# HandCream2040.net
KiCad netlist of a schematic drawn in EAGLE
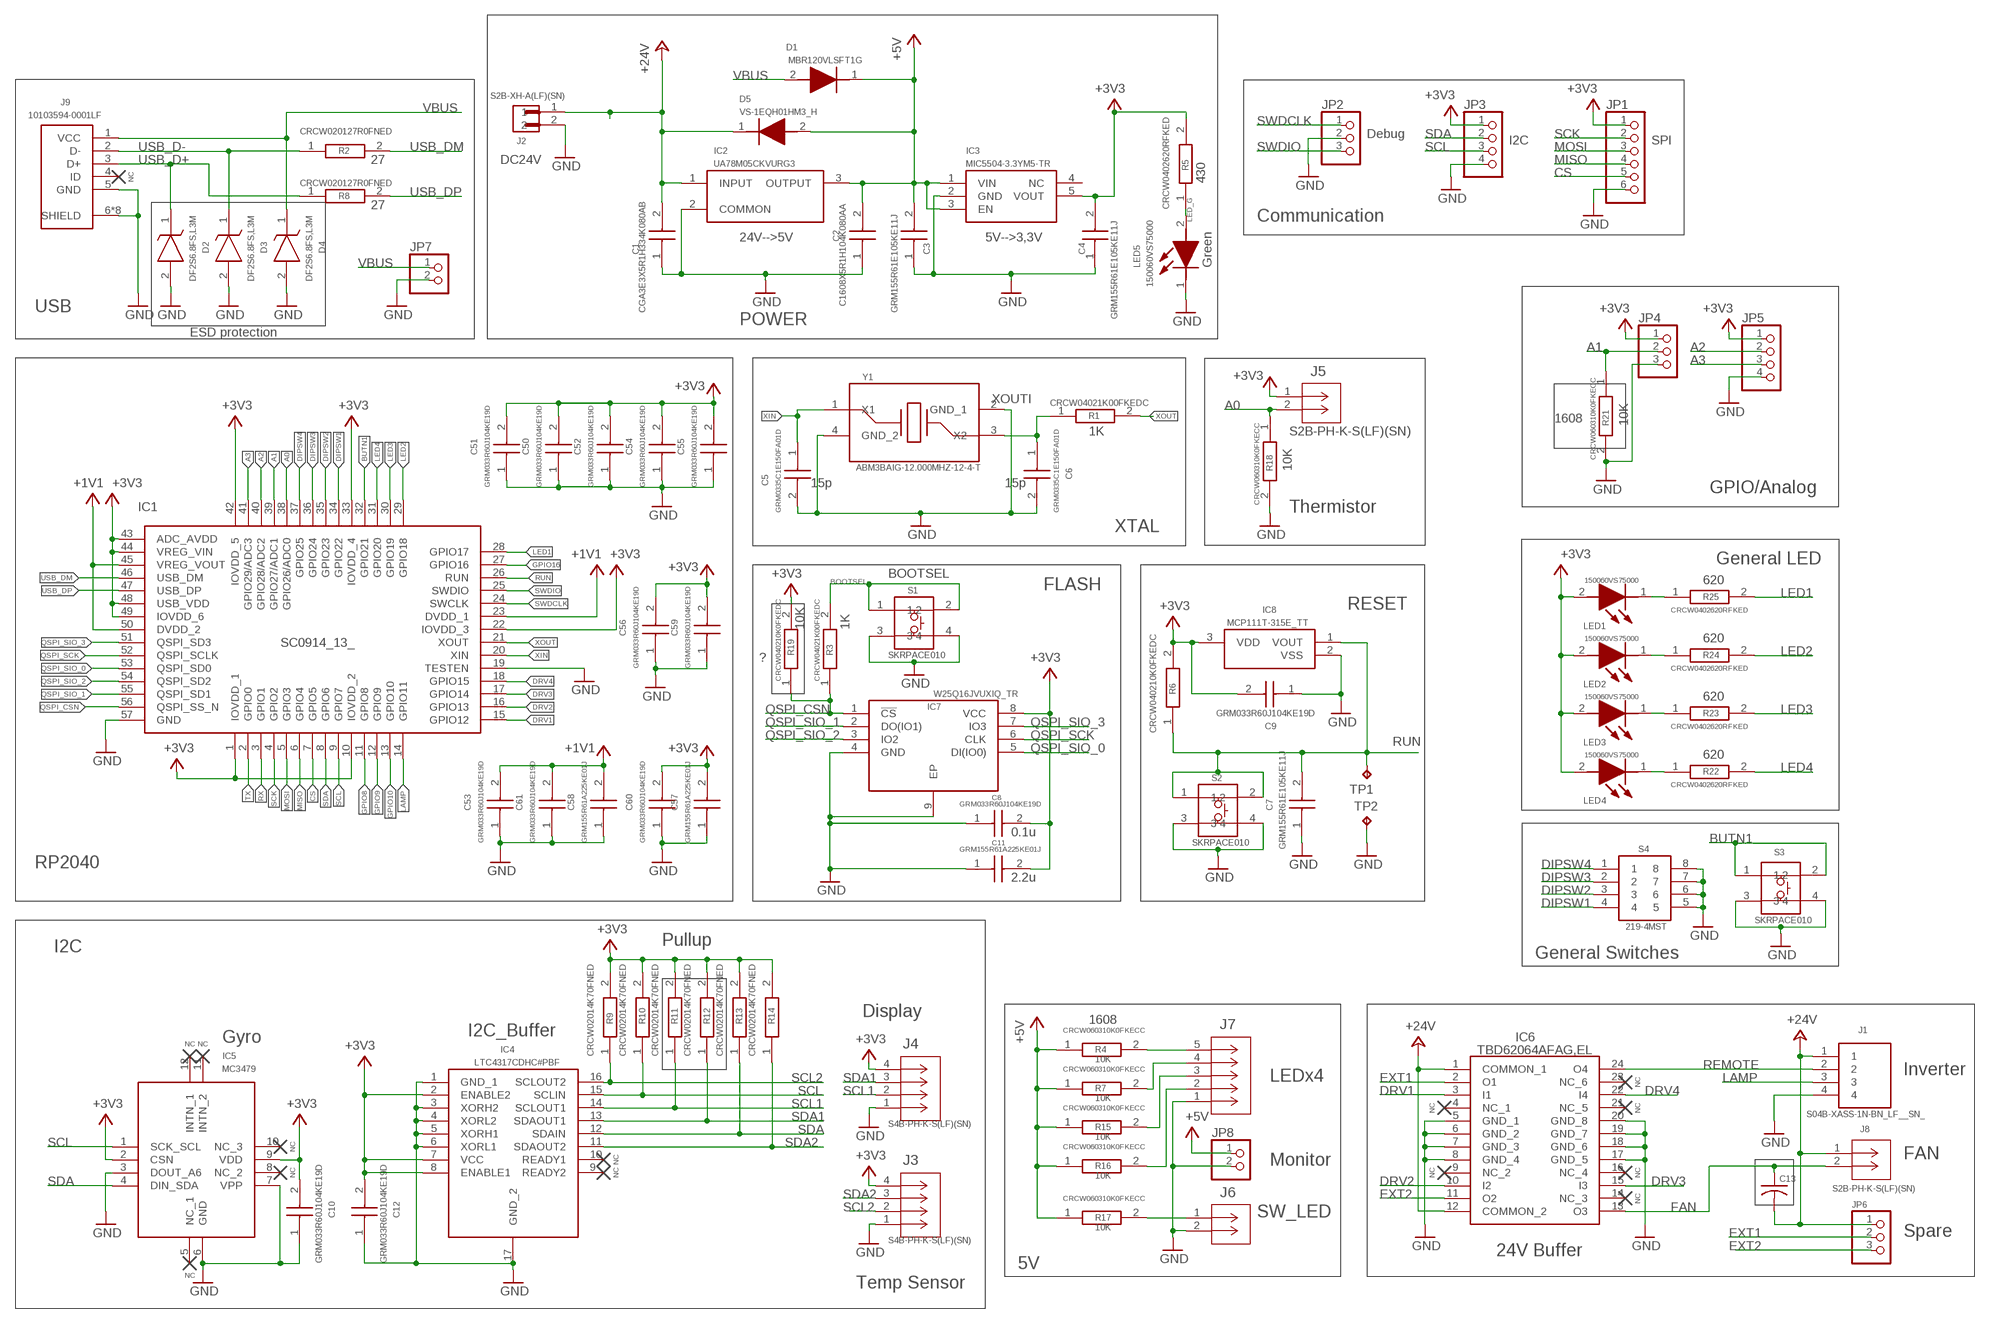
[diagram p0: schematic, sheet 1]

(export (version "E")
  (design (tool "Eeschema 10.0.6"))
  (components
    (comp (ref "C1")
      (value "CGA3E3X5R1H334K080AB")
      (footprint "eagle-import:CAPC1608X90N")
      (fields (field (name "MOUSER_PART_NUMBER") "810-CGA3E3X5R1H334KB"))
      (libsource (lib "eagle-import") (part "CGA3E3X5R1H334K080AB"))
    )
    (comp (ref "C2")
      (value "C1608X5R1H104K080AA")
      (footprint "eagle-import:CAPC1608X80N")
      (fields (field (name "MOUSER_PART_NUMBER") "810-C1608X5R1H104K"))
      (libsource (lib "eagle-import") (part "C1608X5R1H104K080AA"))
    )
    (comp (ref "C3")
      (value "GRM155R61E105KE11J")
      (footprint "eagle-import:CAPC1005X55N")
      (fields (field (name "MOUSER_PART_NUMBER") "81-GRM155R61E105KE1J"))
      (libsource (lib "eagle-import") (part "GRM155R61E105KE11J"))
    )
    (comp (ref "C4")
      (value "GRM155R61E105KE11J")
      (footprint "eagle-import:CAPC1005X55N")
      (fields (field (name "MOUSER_PART_NUMBER") "81-GRM155R61E105KE1J"))
      (libsource (lib "eagle-import") (part "GRM155R61E105KE11J"))
    )
    (comp (ref "C5")
      (value "GRM0335C1E150FA01D")
      (footprint "eagle-import:CAPC0603X33N")
      (fields (field (name "MOUSER_PART_NUMBER") "81-GRM0335C1E150FA1D") (field (name "C") "15p"))
      (libsource (lib "eagle-import") (part "GRM0335C1E150FA01D"))
    )
    (comp (ref "C6")
      (value "GRM0335C1E150FA01D")
      (footprint "eagle-import:CAPC0603X33N")
      (fields (field (name "MOUSER_PART_NUMBER") "81-GRM0335C1E150FA1D") (field (name "C") "15p"))
      (libsource (lib "eagle-import") (part "GRM0335C1E150FA01D"))
    )
    (comp (ref "C7")
      (value "GRM155R61E105KE11J")
      (footprint "eagle-import:CAPC1005X55N")
      (fields (field (name "MOUSER_PART_NUMBER") "81-GRM155R61E105KE1J"))
      (libsource (lib "eagle-import") (part "GRM155R61E105KE11J"))
    )
    (comp (ref "C8")
      (value "GRM033R60J104KE19D")
      (footprint "eagle-import:CAPC0603X33N")
      (fields (field (name "MOUSER_PART_NUMBER") "81-GRM033R60J104KE19") (field (name "C") "0.1u"))
      (libsource (lib "eagle-import") (part "GRM033R60J104KE19D"))
    )
    (comp (ref "C9")
      (value "GRM033R60J104KE19D")
      (footprint "eagle-import:CAPC0603X33N")
      (fields (field (name "MOUSER_PART_NUMBER") "81-GRM033R60J104KE19"))
      (libsource (lib "eagle-import") (part "GRM033R60J104KE19D"))
    )
    (comp (ref "C10")
      (value "GRM033R60J104KE19D")
      (footprint "eagle-import:CAPC0603X33N")
      (fields (field (name "MOUSER_PART_NUMBER") "81-GRM033R60J104KE19"))
      (libsource (lib "eagle-import") (part "GRM033R60J104KE19D"))
    )
    (comp (ref "C11")
      (value "GRM155R61A225KE01J")
      (footprint "eagle-import:CAPC1005X55N")
      (fields (field (name "MOUSER_PART_NUMBER") "81-GRM155R61A225K01J") (field (name "C") "2.2u"))
      (libsource (lib "eagle-import") (part "GRM155R61A225KE01J"))
    )
    (comp (ref "C12")
      (value "GRM033R60J104KE19D")
      (footprint "eagle-import:CAPC0603X33N")
      (fields (field (name "MOUSER_PART_NUMBER") "81-GRM033R60J104KE19"))
      (libsource (lib "eagle-import") (part "GRM033R60J104KE19D"))
    )
    (comp (ref "C13")
      (value "C-US025-024X044")
      (footprint "eagle-import:C025-024X044")
      (libsource (lib "eagle-import") (part "C-US025-024X044"))
    )
    (comp (ref "C50")
      (value "GRM033R60J104KE19D")
      (footprint "eagle-import:CAPC0603X33N")
      (fields (field (name "MOUSER_PART_NUMBER") "81-GRM033R60J104KE19"))
      (libsource (lib "eagle-import") (part "GRM033R60J104KE19D"))
    )
    (comp (ref "C51")
      (value "GRM033R60J104KE19D")
      (footprint "eagle-import:CAPC0603X33N")
      (fields (field (name "MOUSER_PART_NUMBER") "81-GRM033R60J104KE19"))
      (libsource (lib "eagle-import") (part "GRM033R60J104KE19D"))
    )
    (comp (ref "C52")
      (value "GRM033R60J104KE19D")
      (footprint "eagle-import:CAPC0603X33N")
      (fields (field (name "MOUSER_PART_NUMBER") "81-GRM033R60J104KE19"))
      (libsource (lib "eagle-import") (part "GRM033R60J104KE19D"))
    )
    (comp (ref "C53")
      (value "GRM033R60J104KE19D")
      (footprint "eagle-import:CAPC0603X33N")
      (fields (field (name "MOUSER_PART_NUMBER") "81-GRM033R60J104KE19"))
      (libsource (lib "eagle-import") (part "GRM033R60J104KE19D"))
    )
    (comp (ref "C54")
      (value "GRM033R60J104KE19D")
      (footprint "eagle-import:CAPC0603X33N")
      (fields (field (name "MOUSER_PART_NUMBER") "81-GRM033R60J104KE19"))
      (libsource (lib "eagle-import") (part "GRM033R60J104KE19D"))
    )
    (comp (ref "C55")
      (value "GRM033R60J104KE19D")
      (footprint "eagle-import:CAPC0603X33N")
      (fields (field (name "MOUSER_PART_NUMBER") "81-GRM033R60J104KE19"))
      (libsource (lib "eagle-import") (part "GRM033R60J104KE19D"))
    )
    (comp (ref "C56")
      (value "GRM033R60J104KE19D")
      (footprint "eagle-import:CAPC0603X33N")
      (fields (field (name "MOUSER_PART_NUMBER") "81-GRM033R60J104KE19"))
      (libsource (lib "eagle-import") (part "GRM033R60J104KE19D"))
    )
    (comp (ref "C57")
      (value "GRM155R61A225KE01J")
      (footprint "eagle-import:CAPC1005X55N")
      (fields (field (name "MOUSER_PART_NUMBER") "81-GRM155R61A225K01J"))
      (libsource (lib "eagle-import") (part "GRM155R61A225KE01J"))
    )
    (comp (ref "C58")
      (value "GRM155R61A225KE01J")
      (footprint "eagle-import:CAPC1005X55N")
      (fields (field (name "MOUSER_PART_NUMBER") "81-GRM155R61A225K01J"))
      (libsource (lib "eagle-import") (part "GRM155R61A225KE01J"))
    )
    (comp (ref "C59")
      (value "GRM033R60J104KE19D")
      (footprint "eagle-import:CAPC0603X33N")
      (fields (field (name "MOUSER_PART_NUMBER") "81-GRM033R60J104KE19"))
      (libsource (lib "eagle-import") (part "GRM033R60J104KE19D"))
    )
    (comp (ref "C60")
      (value "GRM033R60J104KE19D")
      (footprint "eagle-import:CAPC0603X33N")
      (fields (field (name "MOUSER_PART_NUMBER") "81-GRM033R60J104KE19"))
      (libsource (lib "eagle-import") (part "GRM033R60J104KE19D"))
    )
    (comp (ref "C61")
      (value "GRM033R60J104KE19D")
      (footprint "eagle-import:CAPC0603X33N")
      (fields (field (name "MOUSER_PART_NUMBER") "81-GRM033R60J104KE19"))
      (libsource (lib "eagle-import") (part "GRM033R60J104KE19D"))
    )
    (comp (ref "D1")
      (value "MBR120VLSFT1G")
      (footprint "eagle-import:SODFL3616X98N")
      (fields (field (name "MOUSER_PART_NUMBER") "863-MBR120VLSFT1G"))
      (libsource (lib "eagle-import") (part "MBR120VLSFT1G"))
    )
    (comp (ref "D2")
      (value "DF2S6.8FS,L3M")
      (footprint "eagle-import:SODFL1006X45N")
      (fields (field (name "MOUSER_PART_NUMBER") "757-DF2S68FSL3M"))
      (libsource (lib "eagle-import") (part "DF2S6.8FS,L3M"))
    )
    (comp (ref "D3")
      (value "DF2S6.8FS,L3M")
      (footprint "eagle-import:SODFL1006X45N")
      (fields (field (name "MOUSER_PART_NUMBER") "757-DF2S68FSL3M"))
      (libsource (lib "eagle-import") (part "DF2S6.8FS,L3M"))
    )
    (comp (ref "D4")
      (value "DF2S6.8FS,L3M")
      (footprint "eagle-import:SODFL1006X45N")
      (fields (field (name "MOUSER_PART_NUMBER") "757-DF2S68FSL3M"))
      (libsource (lib "eagle-import") (part "DF2S6.8FS,L3M"))
    )
    (comp (ref "D5")
      (value "VS-1EQH01HM3_H")
      (footprint "eagle-import:VS1EQH01HM3H")
      (fields
        (field (name "MANUFACTURER_PART_NUMBER") "VS-1EQH01HM3/H")
        (field (name "MOUSER_PART_NUMBER") "78-VS-1EQH01HM3/H")
      )
      (libsource (lib "eagle-import") (part "VS-1EQH01HM3_H"))
    )
    (comp (ref "IC1")
      (value "SC0914_13_")
      (footprint "eagle-import:SC091413")
      (fields
        (field (name "MANUFACTURER_PART_NUMBER") "SC0914(13)")
        (field (name "MOUSER_PART_NUMBER") "358-SC091413")
      )
      (libsource (lib "eagle-import") (part "SC0914_13_"))
    )
    (comp (ref "IC2")
      (value "UA78M05CKVURG3")
      (footprint "eagle-import:TPS7A6533QKVURQ1")
      (fields (field (name "MOUSER_PART_NUMBER") "595-UA78M05CKVURG3"))
      (libsource (lib "eagle-import") (part "UA78M05CKVURG3"))
    )
    (comp (ref "IC3")
      (value "MIC5504-3.3YM5-TR")
      (footprint "eagle-import:SOT95P280X145-5N")
      (fields (field (name "MOUSER_PART_NUMBER") "998-MIC5504-3.3YM5TR"))
      (libsource (lib "eagle-import") (part "MIC5504-3.3YM5-TR"))
    )
    (comp (ref "IC4")
      (value "LTC4317CDHC#PBF")
      (footprint "eagle-import:SON50P300X500X80-17N")
      (fields (field (name "MOUSER_PART_NUMBER") "584-LTC4317CDHC#PBF"))
      (libsource (lib "eagle-import") (part "LTC4317CDHC#PBF"))
    )
    (comp (ref "IC5")
      (value "MC3479")
      (footprint "eagle-import:MC3479")
      (fields (field (name "MOUSER_PART_NUMBER") "498-MC3479"))
      (libsource (lib "eagle-import") (part "MC3479"))
    )
    (comp (ref "IC6")
      (value "TBD62064AFAG,EL")
      (footprint "eagle-import:SOP100P800X190-24N")
      (fields (field (name "MOUSER_PART_NUMBER") "757-TBD62064AFAGEHZ"))
      (libsource (lib "eagle-import") (part "TBD62064AFAG,EL"))
    )
    (comp (ref "IC7")
      (value "W25Q16JVUXIQ_TR")
      (footprint "eagle-import:SON50P300X200X60-9N")
      (fields
        (field (name "MANUFACTURER_PART_NUMBER") "W25Q16JVUXIQ TR")
        (field (name "MOUSER_PART_NUMBER") "454-W25Q16JVUXIQTR")
      )
      (libsource (lib "eagle-import") (part "W25Q16JVUXIQ_TR"))
    )
    (comp (ref "IC8")
      (value "MCP111T-315E_TT")
      (footprint "eagle-import:SOT96P237X112-3N")
      (fields
        (field (name "MANUFACTURER_PART_NUMBER") "MCP111T-315E/TT")
        (field (name "MOUSER_PART_NUMBER") "579-MCP111T-315E/TT")
      )
      (libsource (lib "eagle-import") (part "MCP111T-315E_TT"))
    )
    (comp (ref "J1")
      (value "S04B-XASS-1N-BN_LF__SN_")
      (footprint "eagle-import:S04BXASS1NBNLFSN")
      (fields (field (name "MANUFACTURER_PART_NUMBER") "S04B-XASS-1N-BN(LF)(SN)"))
      (libsource (lib "eagle-import") (part "S04B-XASS-1N-BN_LF__SN_"))
    )
    (comp (ref "J2")
      (value "S2B-XH-A(LF)(SN)")
      (footprint "eagle-import:JST_S2B-XH-A(LF)(SN)")
      (fields (field (name "MF") "JST Sales"))
      (libsource (lib "eagle-import") (part "S2B-XH-A(LF)(SN)"))
    )
    (comp (ref "J3")
      (value "S4B-PH-K-S(LF)(SN)")
      (footprint "eagle-import:CONN_S4B-PH-K-S_JST")
      (fields
        (field (name "MANUFACTURER_PART_NUMBER") "S4B-PH-K-S(LF)(SN)")
        (field (name "COPYRIGHT") "Copyright (C) 2023 Ultra Librarian. All rights reserved.")
      )
      (libsource (lib "eagle-import") (part "S4B-PH-K-S(LF)(SN)"))
    )
    (comp (ref "J4")
      (value "S4B-PH-K-S(LF)(SN)")
      (footprint "eagle-import:CONN_S4B-PH-K-S_JST")
      (fields
        (field (name "MANUFACTURER_PART_NUMBER") "S4B-PH-K-S(LF)(SN)")
        (field (name "COPYRIGHT") "Copyright (C) 2023 Ultra Librarian. All rights reserved.")
      )
      (libsource (lib "eagle-import") (part "S4B-PH-K-S(LF)(SN)"))
    )
    (comp (ref "J5")
      (value "S2B-PH-K-S(LF)(SN)")
      (footprint "eagle-import:CONN_S2B-PH-K-S_JST")
      (fields
        (field (name "MANUFACTURER_PART_NUMBER") "S2B-PH-K-S(LF)(SN)")
        (field (name "COPYRIGHT") "Copyright (C) 2023 Ultra Librarian. All rights reserved.")
      )
      (libsource (lib "eagle-import") (part "S2B-PH-K-S(LF)(SN)"))
    )
    (comp (ref "J6")
      (value "S2B-PH-K-S(LF)(SN)")
      (footprint "eagle-import:CONN_S2B-PH-K-S_JST")
      (fields (field (name "COPYRIGHT") "Copyright (C) 2023 Ultra Librarian. All rights reserved."))
      (libsource (lib "eagle-import") (part "S2B-PH-K-S(LF)(SN)"))
    )
    (comp (ref "J7")
      (value "S5B-PH-K-S_(LF)(SN)")
      (footprint "eagle-import:CONN_S5B-PH-K-S_JST")
      (fields
        (field (name "MANUFACTURER_PART_NUMBER") "S5B-PH-K-S (LF)(SN)")
        (field (name "COPYRIGHT") "Copyright (C) 2023 Ultra Librarian. All rights reserved.")
      )
      (libsource (lib "eagle-import") (part "S5B-PH-K-S_(LF)(SN)"))
    )
    (comp (ref "J8")
      (value "S2B-PH-K-S(LF)(SN)")
      (footprint "eagle-import:CONN_S2B-PH-K-S_JST")
      (fields
        (field (name "MANUFACTURER_PART_NUMBER") "S2B-PH-K-S(LF)(SN)")
        (field (name "COPYRIGHT") "Copyright (C) 2023 Ultra Librarian. All rights reserved.")
      )
      (libsource (lib "eagle-import") (part "S2B-PH-K-S(LF)(SN)"))
    )
    (comp (ref "J9")
      (value "10103594-0001LF")
      (footprint "eagle-import:AMPHENOL_10103594-0001LF")
      (fields (field (name "DIGI-KEY_PART_NUMBER") "609-4050-2-ND") (field (name "MF") "Amphenol ICC"))
      (libsource (lib "eagle-import") (part "10103594-0001LF"))
    )
    (comp (ref "JP1")
      (value "PINHD-1X6")
      (footprint "eagle-import:1X06")
      (libsource (lib "eagle-import") (part "PINHD-1X6"))
    )
    (comp (ref "JP2")
      (value "PINHD-1X3")
      (footprint "eagle-import:1X03")
      (libsource (lib "eagle-import") (part "PINHD-1X3"))
    )
    (comp (ref "JP3")
      (value "PINHD-1X4")
      (footprint "eagle-import:1X04")
      (libsource (lib "eagle-import") (part "PINHD-1X4"))
    )
    (comp (ref "JP4")
      (value "PINHD-1X3")
      (footprint "eagle-import:1X03")
      (libsource (lib "eagle-import") (part "PINHD-1X3"))
    )
    (comp (ref "JP5")
      (value "PINHD-1X4")
      (footprint "eagle-import:1X04")
      (libsource (lib "eagle-import") (part "PINHD-1X4"))
    )
    (comp (ref "JP6")
      (value "PINHD-1X3")
      (footprint "eagle-import:1X03")
      (libsource (lib "eagle-import") (part "PINHD-1X3"))
    )
    (comp (ref "JP7")
      (value "PINHD-1X2")
      (footprint "eagle-import:1X02")
      (libsource (lib "eagle-import") (part "PINHD-1X2"))
    )
    (comp (ref "JP8")
      (value "PINHD-1X2")
      (footprint "eagle-import:1X02")
      (libsource (lib "eagle-import") (part "PINHD-1X2"))
    )
    (comp (ref "LED1")
      (value "150060VS75000")
      (footprint "eagle-import:LEDC1608X80N")
      (fields (field (name "MOUSER_PART_NUMBER") "710-150060VS75000"))
      (libsource (lib "eagle-import") (part "150060VS75000"))
    )
    (comp (ref "LED2")
      (value "150060VS75000")
      (footprint "eagle-import:LEDC1608X80N")
      (fields (field (name "MOUSER_PART_NUMBER") "710-150060VS75000"))
      (libsource (lib "eagle-import") (part "150060VS75000"))
    )
    (comp (ref "LED3")
      (value "150060VS75000")
      (footprint "eagle-import:LEDC1608X80N")
      (fields (field (name "MOUSER_PART_NUMBER") "710-150060VS75000"))
      (libsource (lib "eagle-import") (part "150060VS75000"))
    )
    (comp (ref "LED4")
      (value "150060VS75000")
      (footprint "eagle-import:LEDC1608X80N")
      (fields (field (name "MOUSER_PART_NUMBER") "710-150060VS75000"))
      (libsource (lib "eagle-import") (part "150060VS75000"))
    )
    (comp (ref "LED5")
      (value "150060VS75000")
      (footprint "eagle-import:LEDC1608X80N")
      (fields (field (name "MOUSER_PART_NUMBER") "710-150060VS75000"))
      (libsource (lib "eagle-import") (part "150060VS75000"))
    )
    (comp (ref "R1")
      (value "CRCW04021K00FKEDC")
      (footprint "eagle-import:RESC1005X35N")
      (fields (field (name "MOUSER_PART_NUMBER") "71-CRCW04021K00FKEDC") (field (name "R") "1K"))
      (libsource (lib "eagle-import") (part "CRCW04021K00FKEDC"))
    )
    (comp (ref "R2")
      (value "CRCW020127R0FNED")
      (footprint "eagle-import:RESC0603X28N")
      (fields (field (name "MOUSER_PART_NUMBER") "71-CRCW020127R0FNED") (field (name "R") "27"))
      (libsource (lib "eagle-import") (part "CRCW020127R0FNED"))
    )
    (comp (ref "R3")
      (value "CRCW04021K00FKEDC")
      (footprint "eagle-import:RESC1005X35N")
      (fields (field (name "MOUSER_PART_NUMBER") "71-CRCW04021K00FKEDC") (field (name "R") "1K"))
      (libsource (lib "eagle-import") (part "CRCW04021K00FKEDC"))
    )
    (comp (ref "R4")
      (value "CRCW060310K0FKECC")
      (footprint "eagle-import:RESC1608X55N")
      (fields (field (name "MOUSER_PART_NUMBER") "71-CRCW060310K0FKECC") (field (name "R") "10K"))
      (libsource (lib "eagle-import") (part "CRCW060310K0FKECC"))
    )
    (comp (ref "R5")
      (value "CRCW0402620RFKED")
      (footprint "eagle-import:RESC1005X40N")
      (fields (field (name "MOUSER_PART_NUMBER") "71-CRCW0402-620-E3") (field (name "R") "430"))
      (libsource (lib "eagle-import") (part "CRCW0402620RFKED"))
    )
    (comp (ref "R6")
      (value "CRCW040210K0FKEDC")
      (footprint "eagle-import:RESC1005X35N")
      (fields (field (name "MOUSER_PART_NUMBER") "71-CRCW040210K0FKEDC"))
      (libsource (lib "eagle-import") (part "CRCW040210K0FKEDC"))
    )
    (comp (ref "R7")
      (value "CRCW060310K0FKECC")
      (footprint "eagle-import:RESC1608X55N")
      (fields (field (name "MOUSER_PART_NUMBER") "71-CRCW060310K0FKECC") (field (name "R") "10K"))
      (libsource (lib "eagle-import") (part "CRCW060310K0FKECC"))
    )
    (comp (ref "R8")
      (value "CRCW020127R0FNED")
      (footprint "eagle-import:RESC0603X28N")
      (fields (field (name "MOUSER_PART_NUMBER") "71-CRCW020127R0FNED") (field (name "R") "27"))
      (libsource (lib "eagle-import") (part "CRCW020127R0FNED"))
    )
    (comp (ref "R9")
      (value "CRCW02014K70FNED")
      (footprint "eagle-import:RESC0603X28N")
      (fields (field (name "MOUSER_PART_NUMBER") "71-CRCW02014K70FNED"))
      (libsource (lib "eagle-import") (part "CRCW02014K70FNED"))
    )
    (comp (ref "R10")
      (value "CRCW02014K70FNED")
      (footprint "eagle-import:RESC0603X28N")
      (fields (field (name "MOUSER_PART_NUMBER") "71-CRCW02014K70FNED"))
      (libsource (lib "eagle-import") (part "CRCW02014K70FNED"))
    )
    (comp (ref "R11")
      (value "CRCW02014K70FNED")
      (footprint "eagle-import:RESC0603X28N")
      (fields (field (name "MOUSER_PART_NUMBER") "71-CRCW02014K70FNED"))
      (libsource (lib "eagle-import") (part "CRCW02014K70FNED"))
    )
    (comp (ref "R12")
      (value "CRCW02014K70FNED")
      (footprint "eagle-import:RESC0603X28N")
      (fields (field (name "MOUSER_PART_NUMBER") "71-CRCW02014K70FNED"))
      (libsource (lib "eagle-import") (part "CRCW02014K70FNED"))
    )
    (comp (ref "R13")
      (value "CRCW02014K70FNED")
      (footprint "eagle-import:RESC0603X28N")
      (fields (field (name "MOUSER_PART_NUMBER") "71-CRCW02014K70FNED"))
      (libsource (lib "eagle-import") (part "CRCW02014K70FNED"))
    )
    (comp (ref "R14")
      (value "CRCW02014K70FNED")
      (footprint "eagle-import:RESC0603X28N")
      (fields (field (name "MOUSER_PART_NUMBER") "71-CRCW02014K70FNED"))
      (libsource (lib "eagle-import") (part "CRCW02014K70FNED"))
    )
    (comp (ref "R15")
      (value "CRCW060310K0FKECC")
      (footprint "eagle-import:RESC1608X55N")
      (fields (field (name "MOUSER_PART_NUMBER") "71-CRCW060310K0FKECC") (field (name "R") "10K"))
      (libsource (lib "eagle-import") (part "CRCW060310K0FKECC"))
    )
    (comp (ref "R16")
      (value "CRCW060310K0FKECC")
      (footprint "eagle-import:RESC1608X55N")
      (fields (field (name "MOUSER_PART_NUMBER") "71-CRCW060310K0FKECC") (field (name "R") "10K"))
      (libsource (lib "eagle-import") (part "CRCW060310K0FKECC"))
    )
    (comp (ref "R17")
      (value "CRCW060310K0FKECC")
      (footprint "eagle-import:RESC1608X55N")
      (fields (field (name "MOUSER_PART_NUMBER") "71-CRCW060310K0FKECC") (field (name "R") "10K"))
      (libsource (lib "eagle-import") (part "CRCW060310K0FKECC"))
    )
    (comp (ref "R18")
      (value "CRCW060310K0FKECC")
      (footprint "eagle-import:RESC1608X55N")
      (fields (field (name "MOUSER_PART_NUMBER") "71-CRCW060310K0FKECC") (field (name "R") "10K"))
      (libsource (lib "eagle-import") (part "CRCW060310K0FKECC"))
    )
    (comp (ref "R19")
      (value "CRCW040210K0FKEDC")
      (footprint "eagle-import:RESC1005X35N")
      (fields (field (name "MOUSER_PART_NUMBER") "71-CRCW040210K0FKEDC") (field (name "R") "10K"))
      (libsource (lib "eagle-import") (part "CRCW040210K0FKEDC"))
    )
    (comp (ref "R21")
      (value "CRCW060310K0FKECC")
      (footprint "eagle-import:RESC1608X55N")
      (fields (field (name "MOUSER_PART_NUMBER") "71-CRCW060310K0FKECC") (field (name "R") "10K"))
      (libsource (lib "eagle-import") (part "CRCW060310K0FKECC"))
    )
    (comp (ref "R22")
      (value "CRCW0402620RFKED")
      (footprint "eagle-import:RESC1005X40N")
      (fields (field (name "MOUSER_PART_NUMBER") "71-CRCW0402-620-E3") (field (name "R") "620"))
      (libsource (lib "eagle-import") (part "CRCW0402620RFKED"))
    )
    (comp (ref "R23")
      (value "CRCW0402620RFKED")
      (footprint "eagle-import:RESC1005X40N")
      (fields (field (name "MOUSER_PART_NUMBER") "71-CRCW0402-620-E3") (field (name "R") "620"))
      (libsource (lib "eagle-import") (part "CRCW0402620RFKED"))
    )
    (comp (ref "R24")
      (value "CRCW0402620RFKED")
      (footprint "eagle-import:RESC1005X40N")
      (fields (field (name "MOUSER_PART_NUMBER") "71-CRCW0402-620-E3") (field (name "R") "620"))
      (libsource (lib "eagle-import") (part "CRCW0402620RFKED"))
    )
    (comp (ref "R25")
      (value "CRCW0402620RFKED")
      (footprint "eagle-import:RESC1005X40N")
      (fields (field (name "MOUSER_PART_NUMBER") "71-CRCW0402-620-E3") (field (name "R") "620"))
      (libsource (lib "eagle-import") (part "CRCW0402620RFKED"))
    )
    (comp (ref "S1")
      (value "SKRPACE010")
      (footprint "eagle-import:SMT(4.2X3.2)")
      (fields (field (name "MOUSER_PART_NUMBER") "688-SKRPACE010"))
      (libsource (lib "eagle-import") (part "SKRPACE010"))
    )
    (comp (ref "S2")
      (value "SKRPACE010")
      (footprint "eagle-import:SMT(4.2X3.2)")
      (fields (field (name "MOUSER_PART_NUMBER") "688-SKRPACE010"))
      (libsource (lib "eagle-import") (part "SKRPACE010"))
    )
    (comp (ref "S3")
      (value "SKRPACE010")
      (footprint "eagle-import:SMT(4.2X3.2)")
      (fields (field (name "MOUSER_PART_NUMBER") "688-SKRPACE010"))
      (libsource (lib "eagle-import") (part "SKRPACE010"))
    )
    (comp (ref "S4")
      (value "219-4MST")
      (footprint "eagle-import:2194MST")
      (fields (field (name "MOUSER_PART_NUMBER") "774-2194MST"))
      (libsource (lib "eagle-import") (part "219-4MST"))
    )
    (comp (ref "TP1")
      (value "TPB1,27")
      (footprint "eagle-import:B1,27")
      (libsource (lib "eagle-import") (part "TPB1,27"))
    )
    (comp (ref "TP2")
      (value "TPB1,27")
      (footprint "eagle-import:B1,27")
      (libsource (lib "eagle-import") (part "TPB1,27"))
    )
    (comp (ref "Y1")
      (value "ABM3BAIG-12.000MHZ-12-4-T")
      (footprint "eagle-import:ABM3BAIG")
      (fields (field (name "MOUSER_PART_NUMBER") "815-ABM3BAIG1212-4T"))
      (libsource (lib "eagle-import") (part "ABM3BAIG-12.000MHZ-12-4-T"))
    )
  )
  (nets
    (net (code "1") (name "+1V1") (class "Default")
      (node (ref "C53") (pin "2") (pinfunction "2_2") (pintype "bidirectional"))
      (node (ref "C58") (pin "2") (pinfunction "2_2") (pintype "bidirectional"))
      (node (ref "C61") (pin "2") (pinfunction "2_2") (pintype "bidirectional"))
      (node (ref "IC1") (pin "23") (pinfunction "DVDD_1_23") (pintype "bidirectional"))
      (node (ref "IC1") (pin "45") (pinfunction "VREG_VOUT_45") (pintype "bidirectional"))
      (node (ref "IC1") (pin "50") (pinfunction "DVDD_2_50") (pintype "bidirectional"))
    )
    (net (code "2") (name "+3V3") (class "Default")
      (node (ref "C10") (pin "2") (pinfunction "2_2") (pintype "bidirectional"))
      (node (ref "C11") (pin "2") (pinfunction "2_2") (pintype "bidirectional"))
      (node (ref "C12") (pin "2") (pinfunction "2_2") (pintype "bidirectional"))
      (node (ref "C4") (pin "2") (pinfunction "2_2") (pintype "bidirectional"))
      (node (ref "C50") (pin "2") (pinfunction "2_2") (pintype "bidirectional"))
      (node (ref "C51") (pin "2") (pinfunction "2_2") (pintype "bidirectional"))
      (node (ref "C52") (pin "2") (pinfunction "2_2") (pintype "bidirectional"))
      (node (ref "C54") (pin "2") (pinfunction "2_2") (pintype "bidirectional"))
      (node (ref "C55") (pin "2") (pinfunction "2_2") (pintype "bidirectional"))
      (node (ref "C56") (pin "2") (pinfunction "2_2") (pintype "bidirectional"))
      (node (ref "C57") (pin "2") (pinfunction "2_2") (pintype "bidirectional"))
      (node (ref "C59") (pin "2") (pinfunction "2_2") (pintype "bidirectional"))
      (node (ref "C60") (pin "2") (pinfunction "2_2") (pintype "bidirectional"))
      (node (ref "C8") (pin "2") (pinfunction "2_2") (pintype "bidirectional"))
      (node (ref "C9") (pin "2") (pinfunction "2_2") (pintype "bidirectional"))
      (node (ref "IC1") (pin "1") (pinfunction "IOVDD_1_1") (pintype "bidirectional"))
      (node (ref "IC1") (pin "10") (pinfunction "IOVDD_2_10") (pintype "bidirectional"))
      (node (ref "IC1") (pin "22") (pinfunction "IOVDD_3_22") (pintype "bidirectional"))
      (node (ref "IC1") (pin "33") (pinfunction "IOVDD_4_33") (pintype "bidirectional"))
      (node (ref "IC1") (pin "42") (pinfunction "IOVDD_5_42") (pintype "bidirectional"))
      (node (ref "IC1") (pin "43") (pinfunction "ADC_AVDD_43") (pintype "bidirectional"))
      (node (ref "IC1") (pin "44") (pinfunction "VREG_VIN_44") (pintype "bidirectional"))
      (node (ref "IC1") (pin "48") (pinfunction "USB_VDD_48") (pintype "bidirectional"))
      (node (ref "IC1") (pin "49") (pinfunction "IOVDD_6_49") (pintype "bidirectional"))
      (node (ref "IC3") (pin "5") (pinfunction "VOUT_5") (pintype "bidirectional"))
      (node (ref "IC4") (pin "2") (pinfunction "ENABLE2_2") (pintype "bidirectional"))
      (node (ref "IC4") (pin "7") (pinfunction "VCC_7") (pintype "bidirectional"))
      (node (ref "IC4") (pin "8") (pinfunction "ENABLE1_8") (pintype "bidirectional"))
      (node (ref "IC5") (pin "2") (pinfunction "CSN_2") (pintype "bidirectional"))
      (node (ref "IC5") (pin "9") (pinfunction "VDD_9") (pintype "bidirectional"))
      (node (ref "IC7") (pin "8") (pinfunction "VCC_8") (pintype "bidirectional"))
      (node (ref "IC8") (pin "3") (pinfunction "VDD_3") (pintype "bidirectional"))
      (node (ref "J3") (pin "4") (pinfunction "4_4") (pintype "passive"))
      (node (ref "J4") (pin "4") (pinfunction "4_4") (pintype "passive"))
      (node (ref "J5") (pin "1") (pinfunction "1_1") (pintype "passive"))
      (node (ref "JP1") (pin "1") (pinfunction "1_1") (pintype "passive"))
      (node (ref "JP3") (pin "1") (pinfunction "1_1") (pintype "passive"))
      (node (ref "JP4") (pin "1") (pinfunction "1_1") (pintype "passive"))
      (node (ref "JP5") (pin "1") (pinfunction "1_1") (pintype "passive"))
      (node (ref "LED1") (pin "2") (pinfunction "A_2") (pintype "bidirectional"))
      (node (ref "LED2") (pin "2") (pinfunction "A_2") (pintype "bidirectional"))
      (node (ref "LED3") (pin "2") (pinfunction "A_2") (pintype "bidirectional"))
      (node (ref "LED4") (pin "2") (pinfunction "A_2") (pintype "bidirectional"))
      (node (ref "R10") (pin "2") (pinfunction "2_2") (pintype "bidirectional"))
      (node (ref "R11") (pin "2") (pinfunction "2_2") (pintype "bidirectional"))
      (node (ref "R12") (pin "2") (pinfunction "2_2") (pintype "bidirectional"))
      (node (ref "R13") (pin "2") (pinfunction "2_2") (pintype "bidirectional"))
      (node (ref "R14") (pin "2") (pinfunction "2_2") (pintype "bidirectional"))
      (node (ref "R19") (pin "2") (pinfunction "2_2") (pintype "bidirectional"))
      (node (ref "R5") (pin "2") (pinfunction "2_2") (pintype "bidirectional"))
      (node (ref "R6") (pin "2") (pinfunction "2_2") (pintype "bidirectional"))
      (node (ref "R9") (pin "2") (pinfunction "2_2") (pintype "bidirectional"))
    )
    (net (code "3") (name "+5V") (class "Default")
      (node (ref "C2") (pin "2") (pinfunction "2_2") (pintype "bidirectional"))
      (node (ref "C3") (pin "2") (pinfunction "2_2") (pintype "bidirectional"))
      (node (ref "D1") (pin "1") (pinfunction "K_1") (pintype "bidirectional"))
      (node (ref "D5") (pin "2") (pinfunction "A_2") (pintype "bidirectional"))
      (node (ref "IC2") (pin "3") (pinfunction "OUTPUT_3") (pintype "bidirectional"))
      (node (ref "IC3") (pin "1") (pinfunction "VIN_1") (pintype "bidirectional"))
      (node (ref "IC3") (pin "3") (pinfunction "EN_3") (pintype "bidirectional"))
      (node (ref "JP8") (pin "1") (pinfunction "1_1") (pintype "passive"))
      (node (ref "R15") (pin "1") (pinfunction "1_1") (pintype "bidirectional"))
      (node (ref "R16") (pin "1") (pinfunction "1_1") (pintype "bidirectional"))
      (node (ref "R17") (pin "1") (pinfunction "1_1") (pintype "bidirectional"))
      (node (ref "R4") (pin "1") (pinfunction "1_1") (pintype "bidirectional"))
      (node (ref "R7") (pin "1") (pinfunction "1_1") (pintype "bidirectional"))
    )
    (net (code "4") (name "+24V") (class "Default")
      (node (ref "C1") (pin "2") (pinfunction "2_2") (pintype "bidirectional"))
      (node (ref "C13") (pin "2") (pinfunction "2_2") (pintype "passive"))
      (node (ref "D5") (pin "1") (pinfunction "K_1") (pintype "bidirectional"))
      (node (ref "IC2") (pin "1") (pinfunction "INPUT_1") (pintype "bidirectional"))
      (node (ref "IC6") (pin "1") (pinfunction "COMMON_1_1") (pintype "bidirectional"))
      (node (ref "IC6") (pin "12") (pinfunction "COMMON_2_12") (pintype "bidirectional"))
      (node (ref "J1") (pin "1") (pinfunction "1_1") (pintype "bidirectional"))
      (node (ref "J2") (pin "1") (pinfunction "1_1") (pintype "passive"))
      (node (ref "J8") (pin "1") (pinfunction "1_1") (pintype "passive"))
      (node (ref "JP6") (pin "1") (pinfunction "1_1") (pintype "passive"))
    )
    (net (code "5") (name "/BOOTSEL") (class "Default")
      (node (ref "R3") (pin "2") (pinfunction "2_2") (pintype "bidirectional"))
      (node (ref "S1") (pin "1") (pinfunction "1_1") (pintype "bidirectional"))
      (node (ref "S1") (pin "2") (pinfunction "2_2") (pintype "bidirectional"))
    )
    (net (code "6") (name "/EXT1") (class "Default")
      (node (ref "IC6") (pin "2") (pinfunction "O1_2") (pintype "bidirectional"))
      (node (ref "JP6") (pin "2") (pinfunction "2_2") (pintype "passive"))
    )
    (net (code "7") (name "/EXT2") (class "Default")
      (node (ref "IC6") (pin "11") (pinfunction "O2_11") (pintype "bidirectional"))
      (node (ref "JP6") (pin "3") (pinfunction "3_3") (pintype "passive"))
    )
    (net (code "8") (name "/FAN") (class "Default")
      (node (ref "C13") (pin "1") (pinfunction "1_1") (pintype "passive"))
      (node (ref "IC6") (pin "13") (pinfunction "O3_13") (pintype "bidirectional"))
      (node (ref "J8") (pin "2") (pinfunction "2_2") (pintype "passive"))
    )
    (net (code "9") (name "/LED_G") (class "Default")
      (node (ref "LED5") (pin "2") (pinfunction "A_2") (pintype "bidirectional"))
      (node (ref "R5") (pin "1") (pinfunction "1_1") (pintype "bidirectional"))
    )
    (net (code "10") (name "/REMOTE") (class "Default")
      (node (ref "IC6") (pin "24") (pinfunction "O4_24") (pintype "bidirectional"))
      (node (ref "J1") (pin "2") (pinfunction "2_2") (pintype "bidirectional"))
    )
    (net (code "11") (name "/SCL1") (class "Default")
      (node (ref "IC4") (pin "14") (pinfunction "SCLOUT1_14") (pintype "bidirectional"))
      (node (ref "J4") (pin "2") (pinfunction "2_2") (pintype "passive"))
      (node (ref "R11") (pin "1") (pinfunction "1_1") (pintype "bidirectional"))
    )
    (net (code "12") (name "/SCL2") (class "Default")
      (node (ref "IC4") (pin "16") (pinfunction "SCLOUT2_16") (pintype "bidirectional"))
      (node (ref "J3") (pin "2") (pinfunction "2_2") (pintype "passive"))
      (node (ref "R9") (pin "1") (pinfunction "1_1") (pintype "bidirectional"))
    )
    (net (code "13") (name "/SDA1") (class "Default")
      (node (ref "IC4") (pin "13") (pinfunction "SDAOUT1_13") (pintype "bidirectional"))
      (node (ref "J4") (pin "3") (pinfunction "3_3") (pintype "passive"))
      (node (ref "R12") (pin "1") (pinfunction "1_1") (pintype "bidirectional"))
    )
    (net (code "14") (name "/SDA2") (class "Default")
      (node (ref "IC4") (pin "11") (pinfunction "SDAOUT2_11") (pintype "bidirectional"))
      (node (ref "J3") (pin "3") (pinfunction "3_3") (pintype "passive"))
      (node (ref "R14") (pin "1") (pinfunction "1_1") (pintype "bidirectional"))
    )
    (net (code "15") (name "/USB_D+") (class "Default")
      (node (ref "D2") (pin "1") (pinfunction "K_1") (pintype "bidirectional"))
      (node (ref "J9") (pin "3") (pinfunction "D+_3") (pintype "bidirectional"))
      (node (ref "R8") (pin "1") (pinfunction "1_1") (pintype "bidirectional"))
    )
    (net (code "16") (name "/USB_D-") (class "Default")
      (node (ref "D3") (pin "1") (pinfunction "K_1") (pintype "bidirectional"))
      (node (ref "J9") (pin "2") (pinfunction "D-_2") (pintype "bidirectional"))
      (node (ref "R2") (pin "1") (pinfunction "1_1") (pintype "bidirectional"))
    )
    (net (code "17") (name "/VBUS") (class "Default")
      (node (ref "D1") (pin "2") (pinfunction "A_2") (pintype "bidirectional"))
      (node (ref "D4") (pin "1") (pinfunction "K_1") (pintype "bidirectional"))
      (node (ref "J9") (pin "1") (pinfunction "VCC_1") (pintype "power_in"))
      (node (ref "JP7") (pin "1") (pinfunction "1_1") (pintype "passive"))
    )
    (net (code "18") (name "/XOUTI") (class "Default")
      (node (ref "C6") (pin "1") (pinfunction "1_1") (pintype "bidirectional"))
      (node (ref "R1") (pin "1") (pinfunction "1_1") (pintype "bidirectional"))
      (node (ref "Y1") (pin "3") (pinfunction "X2_3") (pintype "bidirectional"))
    )
    (net (code "19") (name "A0") (class "Default")
      (node (ref "IC1") (pin "38") (pinfunction "GPIO26/ADC0_38") (pintype "bidirectional"))
      (node (ref "J5") (pin "2") (pinfunction "2_2") (pintype "passive"))
      (node (ref "R18") (pin "1") (pinfunction "1_1") (pintype "bidirectional"))
    )
    (net (code "20") (name "A1") (class "Default")
      (node (ref "IC1") (pin "39") (pinfunction "GPIO27/ADC1_39") (pintype "bidirectional"))
      (node (ref "JP4") (pin "2") (pinfunction "2_2") (pintype "passive"))
      (node (ref "R21") (pin "1") (pinfunction "1_1") (pintype "bidirectional"))
    )
    (net (code "21") (name "A2") (class "Default")
      (node (ref "IC1") (pin "40") (pinfunction "GPIO28/ADC2_40") (pintype "bidirectional"))
      (node (ref "JP5") (pin "2") (pinfunction "2_2") (pintype "passive"))
    )
    (net (code "22") (name "A3") (class "Default")
      (node (ref "IC1") (pin "41") (pinfunction "GPIO29/ADC3_41") (pintype "bidirectional"))
      (node (ref "JP5") (pin "3") (pinfunction "3_3") (pintype "passive"))
    )
    (net (code "23") (name "BUTN1") (class "Default")
      (node (ref "IC1") (pin "32") (pinfunction "GPIO21_32") (pintype "bidirectional"))
      (node (ref "S3") (pin "1") (pinfunction "1_1") (pintype "bidirectional"))
      (node (ref "S3") (pin "2") (pinfunction "2_2") (pintype "bidirectional"))
    )
    (net (code "24") (name "CS") (class "Default")
      (node (ref "IC1") (pin "7") (pinfunction "GPIO5_7") (pintype "bidirectional"))
      (node (ref "JP1") (pin "5") (pinfunction "5_5") (pintype "passive"))
    )
    (net (code "25") (name "DIPSW1") (class "Default")
      (node (ref "IC1") (pin "34") (pinfunction "GPIO22_34") (pintype "bidirectional"))
      (node (ref "S4") (pin "4") (pinfunction "4_4") (pintype "bidirectional"))
    )
    (net (code "26") (name "DIPSW2") (class "Default")
      (node (ref "IC1") (pin "35") (pinfunction "GPIO23_35") (pintype "bidirectional"))
      (node (ref "S4") (pin "3") (pinfunction "3_3") (pintype "bidirectional"))
    )
    (net (code "27") (name "DIPSW3") (class "Default")
      (node (ref "IC1") (pin "36") (pinfunction "GPIO24_36") (pintype "bidirectional"))
      (node (ref "S4") (pin "2") (pinfunction "2_2") (pintype "bidirectional"))
    )
    (net (code "28") (name "DIPSW4") (class "Default")
      (node (ref "IC1") (pin "37") (pinfunction "GPIO25_37") (pintype "bidirectional"))
      (node (ref "S4") (pin "1") (pinfunction "1_1") (pintype "bidirectional"))
    )
    (net (code "29") (name "DRV1") (class "Default")
      (node (ref "IC1") (pin "15") (pinfunction "GPIO12_15") (pintype "bidirectional"))
      (node (ref "IC6") (pin "3") (pinfunction "I1_3") (pintype "bidirectional"))
    )
    (net (code "30") (name "DRV2") (class "Default")
      (node (ref "IC1") (pin "16") (pinfunction "GPIO13_16") (pintype "bidirectional"))
      (node (ref "IC6") (pin "10") (pinfunction "I2_10") (pintype "bidirectional"))
    )
    (net (code "31") (name "DRV3") (class "Default")
      (node (ref "IC1") (pin "17") (pinfunction "GPIO14_17") (pintype "bidirectional"))
      (node (ref "IC6") (pin "15") (pinfunction "I3_15") (pintype "bidirectional"))
    )
    (net (code "32") (name "DRV4") (class "Default")
      (node (ref "IC1") (pin "18") (pinfunction "GPIO15_18") (pintype "bidirectional"))
      (node (ref "IC6") (pin "22") (pinfunction "I4_22") (pintype "bidirectional"))
    )
    (net (code "33") (name "GND") (class "Default")
      (node (ref "C1") (pin "1") (pinfunction "1_1") (pintype "bidirectional"))
      (node (ref "C10") (pin "1") (pinfunction "1_1") (pintype "bidirectional"))
      (node (ref "C11") (pin "1") (pinfunction "1_1") (pintype "bidirectional"))
      (node (ref "C12") (pin "1") (pinfunction "1_1") (pintype "bidirectional"))
      (node (ref "C2") (pin "1") (pinfunction "1_1") (pintype "bidirectional"))
      (node (ref "C3") (pin "1") (pinfunction "1_1") (pintype "bidirectional"))
      (node (ref "C4") (pin "1") (pinfunction "1_1") (pintype "bidirectional"))
      (node (ref "C5") (pin "2") (pinfunction "2_2") (pintype "bidirectional"))
      (node (ref "C50") (pin "1") (pinfunction "1_1") (pintype "bidirectional"))
      (node (ref "C51") (pin "1") (pinfunction "1_1") (pintype "bidirectional"))
      (node (ref "C52") (pin "1") (pinfunction "1_1") (pintype "bidirectional"))
      (node (ref "C53") (pin "1") (pinfunction "1_1") (pintype "bidirectional"))
      (node (ref "C54") (pin "1") (pinfunction "1_1") (pintype "bidirectional"))
      (node (ref "C55") (pin "1") (pinfunction "1_1") (pintype "bidirectional"))
      (node (ref "C56") (pin "1") (pinfunction "1_1") (pintype "bidirectional"))
      (node (ref "C57") (pin "1") (pinfunction "1_1") (pintype "bidirectional"))
      (node (ref "C58") (pin "1") (pinfunction "1_1") (pintype "bidirectional"))
      (node (ref "C59") (pin "1") (pinfunction "1_1") (pintype "bidirectional"))
      (node (ref "C6") (pin "2") (pinfunction "2_2") (pintype "bidirectional"))
      (node (ref "C60") (pin "1") (pinfunction "1_1") (pintype "bidirectional"))
      (node (ref "C61") (pin "1") (pinfunction "1_1") (pintype "bidirectional"))
      (node (ref "C7") (pin "1") (pinfunction "1_1") (pintype "bidirectional"))
      (node (ref "C8") (pin "1") (pinfunction "1_1") (pintype "bidirectional"))
      (node (ref "C9") (pin "1") (pinfunction "1_1") (pintype "bidirectional"))
      (node (ref "D2") (pin "2") (pinfunction "A_2") (pintype "bidirectional"))
      (node (ref "D3") (pin "2") (pinfunction "A_2") (pintype "bidirectional"))
      (node (ref "D4") (pin "2") (pinfunction "A_2") (pintype "bidirectional"))
      (node (ref "IC1") (pin "19") (pinfunction "TESTEN_19") (pintype "bidirectional"))
      (node (ref "IC1") (pin "57") (pinfunction "GND_57") (pintype "bidirectional"))
      (node (ref "IC2") (pin "2") (pinfunction "COMMON_2") (pintype "bidirectional"))
      (node (ref "IC3") (pin "2") (pinfunction "GND_2") (pintype "bidirectional"))
      (node (ref "IC4") (pin "1") (pinfunction "GND_1_1") (pintype "bidirectional"))
      (node (ref "IC4") (pin "17") (pinfunction "GND_2_17") (pintype "bidirectional"))
      (node (ref "IC4") (pin "3") (pinfunction "XORH2_3") (pintype "bidirectional"))
      (node (ref "IC4") (pin "4") (pinfunction "XORL2_4") (pintype "bidirectional"))
      (node (ref "IC4") (pin "5") (pinfunction "XORH1_5") (pintype "bidirectional"))
      (node (ref "IC4") (pin "6") (pinfunction "XORL1_6") (pintype "bidirectional"))
      (node (ref "IC5") (pin "3") (pinfunction "DOUT_A6_3") (pintype "bidirectional"))
      (node (ref "IC5") (pin "6") (pinfunction "GND_6") (pintype "bidirectional"))
      (node (ref "IC5") (pin "7") (pinfunction "VPP_7") (pintype "bidirectional"))
      (node (ref "IC6") (pin "17") (pinfunction "GND_5_17") (pintype "bidirectional"))
      (node (ref "IC6") (pin "18") (pinfunction "GND_6_18") (pintype "bidirectional"))
      (node (ref "IC6") (pin "19") (pinfunction "GND_7_19") (pintype "bidirectional"))
      (node (ref "IC6") (pin "20") (pinfunction "GND_8_20") (pintype "bidirectional"))
      (node (ref "IC6") (pin "5") (pinfunction "GND_1_5") (pintype "bidirectional"))
      (node (ref "IC6") (pin "6") (pinfunction "GND_2_6") (pintype "bidirectional"))
      (node (ref "IC6") (pin "7") (pinfunction "GND_3_7") (pintype "bidirectional"))
      (node (ref "IC6") (pin "8") (pinfunction "GND_4_8") (pintype "bidirectional"))
      (node (ref "IC7") (pin "4") (pinfunction "GND_4") (pintype "bidirectional"))
      (node (ref "IC7") (pin "9") (pinfunction "EP_9") (pintype "bidirectional"))
      (node (ref "IC8") (pin "2") (pinfunction "VSS_2") (pintype "bidirectional"))
      (node (ref "J1") (pin "4") (pinfunction "4_4") (pintype "bidirectional"))
      (node (ref "J2") (pin "2") (pinfunction "2_2") (pintype "passive"))
      (node (ref "J3") (pin "1") (pinfunction "1_1") (pintype "passive"))
      (node (ref "J4") (pin "1") (pinfunction "1_1") (pintype "passive"))
      (node (ref "J6") (pin "2") (pinfunction "2_2") (pintype "passive"))
      (node (ref "J7") (pin "1") (pinfunction "1_1") (pintype "passive"))
      (node (ref "J9") (pin "10") (pinfunction "SHIELD_10") (pintype "passive"))
      (node (ref "J9") (pin "11") (pinfunction "SHIELD_11") (pintype "passive"))
      (node (ref "J9") (pin "5") (pinfunction "GND_5") (pintype "power_in"))
      (node (ref "J9") (pin "6") (pinfunction "SHIELD_6") (pintype "passive"))
      (node (ref "J9") (pin "7") (pinfunction "SHIELD_7") (pintype "passive"))
      (node (ref "J9") (pin "8") (pinfunction "SHIELD_8") (pintype "passive"))
      (node (ref "J9") (pin "9") (pinfunction "SHIELD_9") (pintype "passive"))
      (node (ref "J9") (pin "S1") (pinfunction "SHIELD_S1") (pintype "passive"))
      (node (ref "J9") (pin "S2") (pinfunction "SHIELD_S2") (pintype "passive"))
      (node (ref "JP1") (pin "6") (pinfunction "6_6") (pintype "passive"))
      (node (ref "JP2") (pin "2") (pinfunction "2_2") (pintype "passive"))
      (node (ref "JP3") (pin "4") (pinfunction "4_4") (pintype "passive"))
      (node (ref "JP4") (pin "3") (pinfunction "3_3") (pintype "passive"))
      (node (ref "JP5") (pin "4") (pinfunction "4_4") (pintype "passive"))
      (node (ref "JP7") (pin "2") (pinfunction "2_2") (pintype "passive"))
      (node (ref "JP8") (pin "2") (pinfunction "2_2") (pintype "passive"))
      (node (ref "LED5") (pin "1") (pinfunction "K_1") (pintype "bidirectional"))
      (node (ref "R18") (pin "2") (pinfunction "2_2") (pintype "bidirectional"))
      (node (ref "R21") (pin "2") (pinfunction "2_2") (pintype "bidirectional"))
      (node (ref "S1") (pin "3") (pinfunction "3_3") (pintype "bidirectional"))
      (node (ref "S1") (pin "4") (pinfunction "4_4") (pintype "bidirectional"))
      (node (ref "S2") (pin "3") (pinfunction "3_3") (pintype "bidirectional"))
      (node (ref "S2") (pin "4") (pinfunction "4_4") (pintype "bidirectional"))
      (node (ref "S3") (pin "3") (pinfunction "3_3") (pintype "bidirectional"))
      (node (ref "S3") (pin "4") (pinfunction "4_4") (pintype "bidirectional"))
      (node (ref "S4") (pin "5") (pinfunction "5_5") (pintype "bidirectional"))
      (node (ref "S4") (pin "6") (pinfunction "6_6") (pintype "bidirectional"))
      (node (ref "S4") (pin "7") (pinfunction "7_7") (pintype "bidirectional"))
      (node (ref "S4") (pin "8") (pinfunction "8_8") (pintype "bidirectional"))
      (node (ref "TP2") (pin "TP") (pinfunction "TP_TP") (pintype "input"))
      (node (ref "Y1") (pin "2") (pinfunction "GND_1_2") (pintype "bidirectional"))
      (node (ref "Y1") (pin "4") (pinfunction "GND_2_4") (pintype "bidirectional"))
    )
    (net (code "34") (name "GPIO8") (class "Default")
      (node (ref "IC1") (pin "11") (pinfunction "GPIO8_11") (pintype "bidirectional"))
    )
    (net (code "35") (name "GPIO9") (class "Default")
      (node (ref "IC1") (pin "12") (pinfunction "GPIO9_12") (pintype "bidirectional"))
    )
    (net (code "36") (name "GPIO10") (class "Default")
      (node (ref "IC1") (pin "13") (pinfunction "GPIO10_13") (pintype "bidirectional"))
    )
    (net (code "37") (name "GPIO16") (class "Default")
      (node (ref "IC1") (pin "27") (pinfunction "GPIO16_27") (pintype "bidirectional"))
    )
    (net (code "38") (name "LAMP") (class "Default")
      (node (ref "IC1") (pin "14") (pinfunction "GPIO11_14") (pintype "bidirectional"))
      (node (ref "J1") (pin "3") (pinfunction "3_3") (pintype "bidirectional"))
    )
    (net (code "39") (name "LED1") (class "Default")
      (node (ref "IC1") (pin "28") (pinfunction "GPIO17_28") (pintype "bidirectional"))
      (node (ref "R25") (pin "2") (pinfunction "2_2") (pintype "bidirectional"))
    )
    (net (code "40") (name "LED2") (class "Default")
      (node (ref "IC1") (pin "29") (pinfunction "GPIO18_29") (pintype "bidirectional"))
      (node (ref "R24") (pin "2") (pinfunction "2_2") (pintype "bidirectional"))
    )
    (net (code "41") (name "LED3") (class "Default")
      (node (ref "IC1") (pin "30") (pinfunction "GPIO19_30") (pintype "bidirectional"))
      (node (ref "R23") (pin "2") (pinfunction "2_2") (pintype "bidirectional"))
    )
    (net (code "42") (name "LED4") (class "Default")
      (node (ref "IC1") (pin "31") (pinfunction "GPIO20_31") (pintype "bidirectional"))
      (node (ref "R22") (pin "2") (pinfunction "2_2") (pintype "bidirectional"))
    )
    (net (code "43") (name "MISO") (class "Default")
      (node (ref "IC1") (pin "6") (pinfunction "GPIO4_6") (pintype "bidirectional"))
      (node (ref "JP1") (pin "4") (pinfunction "4_4") (pintype "passive"))
    )
    (net (code "44") (name "MOSI") (class "Default")
      (node (ref "IC1") (pin "5") (pinfunction "GPIO3_5") (pintype "bidirectional"))
      (node (ref "JP1") (pin "3") (pinfunction "3_3") (pintype "passive"))
    )
    (net (code "45") (name "Net-(J6-Pad1)") (class "Default")
      (node (ref "J6") (pin "1") (pinfunction "1_1") (pintype "passive"))
      (node (ref "R17") (pin "2") (pinfunction "2_2") (pintype "bidirectional"))
    )
    (net (code "46") (name "Net-(J7-Pad2)") (class "Default")
      (node (ref "J7") (pin "2") (pinfunction "2_2") (pintype "passive"))
      (node (ref "R16") (pin "2") (pinfunction "2_2") (pintype "bidirectional"))
    )
    (net (code "47") (name "Net-(J7-Pad3)") (class "Default")
      (node (ref "J7") (pin "3") (pinfunction "3_3") (pintype "passive"))
      (node (ref "R15") (pin "2") (pinfunction "2_2") (pintype "bidirectional"))
    )
    (net (code "48") (name "Net-(J7-Pad4)") (class "Default")
      (node (ref "J7") (pin "4") (pinfunction "4_4") (pintype "passive"))
      (node (ref "R7") (pin "2") (pinfunction "2_2") (pintype "bidirectional"))
    )
    (net (code "49") (name "Net-(J7-Pad5)") (class "Default")
      (node (ref "J7") (pin "5") (pinfunction "5_5") (pintype "passive"))
      (node (ref "R4") (pin "2") (pinfunction "2_2") (pintype "bidirectional"))
    )
    (net (code "50") (name "Net-(LED1-K)") (class "Default")
      (node (ref "LED1") (pin "1") (pinfunction "K_1") (pintype "bidirectional"))
      (node (ref "R25") (pin "1") (pinfunction "1_1") (pintype "bidirectional"))
    )
    (net (code "51") (name "Net-(LED2-K)") (class "Default")
      (node (ref "LED2") (pin "1") (pinfunction "K_1") (pintype "bidirectional"))
      (node (ref "R24") (pin "1") (pinfunction "1_1") (pintype "bidirectional"))
    )
    (net (code "52") (name "Net-(LED3-K)") (class "Default")
      (node (ref "LED3") (pin "1") (pinfunction "K_1") (pintype "bidirectional"))
      (node (ref "R23") (pin "1") (pinfunction "1_1") (pintype "bidirectional"))
    )
    (net (code "53") (name "Net-(LED4-K)") (class "Default")
      (node (ref "LED4") (pin "1") (pinfunction "K_1") (pintype "bidirectional"))
      (node (ref "R22") (pin "1") (pinfunction "1_1") (pintype "bidirectional"))
    )
    (net (code "54") (name "QSPI_CSN") (class "Default")
      (node (ref "IC1") (pin "56") (pinfunction "QSPI_SS_N_56") (pintype "bidirectional"))
      (node (ref "IC7") (pin "1") (pinfunction "~{CS}_1") (pintype "bidirectional"))
      (node (ref "R19") (pin "1") (pinfunction "1_1") (pintype "bidirectional"))
      (node (ref "R3") (pin "1") (pinfunction "1_1") (pintype "bidirectional"))
    )
    (net (code "55") (name "QSPI_SCK") (class "Default")
      (node (ref "IC1") (pin "52") (pinfunction "QSPI_SCLK_52") (pintype "bidirectional"))
      (node (ref "IC7") (pin "6") (pinfunction "CLK_6") (pintype "bidirectional"))
    )
    (net (code "56") (name "QSPI_SIO_0") (class "Default")
      (node (ref "IC1") (pin "53") (pinfunction "QSPI_SD0_53") (pintype "bidirectional"))
      (node (ref "IC7") (pin "5") (pinfunction "DI(IO0)_5") (pintype "bidirectional"))
    )
    (net (code "57") (name "QSPI_SIO_1") (class "Default")
      (node (ref "IC1") (pin "55") (pinfunction "QSPI_SD1_55") (pintype "bidirectional"))
      (node (ref "IC7") (pin "2") (pinfunction "DO(IO1)_2") (pintype "bidirectional"))
    )
    (net (code "58") (name "QSPI_SIO_2") (class "Default")
      (node (ref "IC1") (pin "54") (pinfunction "QSPI_SD2_54") (pintype "bidirectional"))
      (node (ref "IC7") (pin "3") (pinfunction "IO2_3") (pintype "bidirectional"))
    )
    (net (code "59") (name "QSPI_SIO_3") (class "Default")
      (node (ref "IC1") (pin "51") (pinfunction "QSPI_SD3_51") (pintype "bidirectional"))
      (node (ref "IC7") (pin "7") (pinfunction "IO3_7") (pintype "bidirectional"))
    )
    (net (code "60") (name "RUN") (class "Default")
      (node (ref "C7") (pin "2") (pinfunction "2_2") (pintype "bidirectional"))
      (node (ref "IC1") (pin "26") (pinfunction "RUN_26") (pintype "bidirectional"))
      (node (ref "IC8") (pin "1") (pinfunction "VOUT_1") (pintype "bidirectional"))
      (node (ref "R6") (pin "1") (pinfunction "1_1") (pintype "bidirectional"))
      (node (ref "S2") (pin "1") (pinfunction "1_1") (pintype "bidirectional"))
      (node (ref "S2") (pin "2") (pinfunction "2_2") (pintype "bidirectional"))
      (node (ref "TP1") (pin "TP") (pinfunction "TP_TP") (pintype "input"))
    )
    (net (code "61") (name "RX") (class "Default")
      (node (ref "IC1") (pin "3") (pinfunction "GPIO1_3") (pintype "bidirectional"))
    )
    (net (code "62") (name "SCK") (class "Default")
      (node (ref "IC1") (pin "4") (pinfunction "GPIO2_4") (pintype "bidirectional"))
      (node (ref "JP1") (pin "2") (pinfunction "2_2") (pintype "passive"))
    )
    (net (code "63") (name "SCL") (class "Default")
      (node (ref "IC1") (pin "9") (pinfunction "GPIO7_9") (pintype "bidirectional"))
      (node (ref "IC4") (pin "15") (pinfunction "SCLIN_15") (pintype "bidirectional"))
      (node (ref "IC5") (pin "1") (pinfunction "SCK_SCL_1") (pintype "bidirectional"))
      (node (ref "JP3") (pin "3") (pinfunction "3_3") (pintype "passive"))
      (node (ref "R10") (pin "1") (pinfunction "1_1") (pintype "bidirectional"))
    )
    (net (code "64") (name "SDA") (class "Default")
      (node (ref "IC1") (pin "8") (pinfunction "GPIO6_8") (pintype "bidirectional"))
      (node (ref "IC4") (pin "12") (pinfunction "SDAIN_12") (pintype "bidirectional"))
      (node (ref "IC5") (pin "4") (pinfunction "DIN_SDA_4") (pintype "bidirectional"))
      (node (ref "JP3") (pin "2") (pinfunction "2_2") (pintype "passive"))
      (node (ref "R13") (pin "1") (pinfunction "1_1") (pintype "bidirectional"))
    )
    (net (code "65") (name "SWDCLK") (class "Default")
      (node (ref "IC1") (pin "24") (pinfunction "SWCLK_24") (pintype "bidirectional"))
      (node (ref "JP2") (pin "1") (pinfunction "1_1") (pintype "passive"))
    )
    (net (code "66") (name "SWDIO") (class "Default")
      (node (ref "IC1") (pin "25") (pinfunction "SWDIO_25") (pintype "bidirectional"))
      (node (ref "JP2") (pin "3") (pinfunction "3_3") (pintype "passive"))
    )
    (net (code "67") (name "TX") (class "Default")
      (node (ref "IC1") (pin "2") (pinfunction "GPIO0_2") (pintype "bidirectional"))
    )
    (net (code "68") (name "USB_DM") (class "Default")
      (node (ref "IC1") (pin "46") (pinfunction "USB_DM_46") (pintype "bidirectional"))
      (node (ref "R2") (pin "2") (pinfunction "2_2") (pintype "bidirectional"))
    )
    (net (code "69") (name "USB_DP") (class "Default")
      (node (ref "IC1") (pin "47") (pinfunction "USB_DP_47") (pintype "bidirectional"))
      (node (ref "R8") (pin "2") (pinfunction "2_2") (pintype "bidirectional"))
    )
    (net (code "70") (name "XIN") (class "Default")
      (node (ref "C5") (pin "1") (pinfunction "1_1") (pintype "bidirectional"))
      (node (ref "IC1") (pin "20") (pinfunction "XIN_20") (pintype "bidirectional"))
      (node (ref "Y1") (pin "1") (pinfunction "X1_1") (pintype "bidirectional"))
    )
    (net (code "71") (name "XOUT") (class "Default")
      (node (ref "IC1") (pin "21") (pinfunction "XOUT_21") (pintype "bidirectional"))
      (node (ref "R1") (pin "2") (pinfunction "2_2") (pintype "bidirectional"))
    )
    (net (code "72") (name "unconnected-(IC3-NC-Pad4)") (class "Default")
      (node (ref "IC3") (pin "4") (pinfunction "NC_4") (pintype "no_connect"))
    )
    (net (code "73") (name "unconnected-(IC4-READY1-Pad10)") (class "Default")
      (node (ref "IC4") (pin "10") (pinfunction "READY1_10") (pintype "bidirectional"))
    )
    (net (code "74") (name "unconnected-(IC4-READY2-Pad9)") (class "Default")
      (node (ref "IC4") (pin "9") (pinfunction "READY2_9") (pintype "bidirectional"))
    )
    (net (code "75") (name "unconnected-(IC5-INTN_1-Pad12)") (class "Default")
      (node (ref "IC5") (pin "12") (pinfunction "INTN_1_12") (pintype "bidirectional"))
    )
    (net (code "76") (name "unconnected-(IC5-INTN_2-Pad11)") (class "Default")
      (node (ref "IC5") (pin "11") (pinfunction "INTN_2_11") (pintype "bidirectional"))
    )
    (net (code "77") (name "unconnected-(IC5-NC_1-Pad5)") (class "Default")
      (node (ref "IC5") (pin "5") (pinfunction "NC_1_5") (pintype "bidirectional"))
    )
    (net (code "78") (name "unconnected-(IC5-NC_2-Pad8)") (class "Default")
      (node (ref "IC5") (pin "8") (pinfunction "NC_2_8") (pintype "bidirectional"))
    )
    (net (code "79") (name "unconnected-(IC5-NC_3-Pad10)") (class "Default")
      (node (ref "IC5") (pin "10") (pinfunction "NC_3_10") (pintype "bidirectional"))
    )
    (net (code "80") (name "unconnected-(IC6-NC_1-Pad4)") (class "Default")
      (node (ref "IC6") (pin "4") (pinfunction "NC_1_4") (pintype "bidirectional"))
    )
    (net (code "81") (name "unconnected-(IC6-NC_2-Pad9)") (class "Default")
      (node (ref "IC6") (pin "9") (pinfunction "NC_2_9") (pintype "bidirectional"))
    )
    (net (code "82") (name "unconnected-(IC6-NC_3-Pad14)") (class "Default")
      (node (ref "IC6") (pin "14") (pinfunction "NC_3_14") (pintype "bidirectional"))
    )
    (net (code "83") (name "unconnected-(IC6-NC_4-Pad16)") (class "Default")
      (node (ref "IC6") (pin "16") (pinfunction "NC_4_16") (pintype "bidirectional"))
    )
    (net (code "84") (name "unconnected-(IC6-NC_5-Pad21)") (class "Default")
      (node (ref "IC6") (pin "21") (pinfunction "NC_5_21") (pintype "bidirectional"))
    )
    (net (code "85") (name "unconnected-(IC6-NC_6-Pad23)") (class "Default")
      (node (ref "IC6") (pin "23") (pinfunction "NC_6_23") (pintype "bidirectional"))
    )
    (net (code "86") (name "unconnected-(J9-ID-Pad4)") (class "Default")
      (node (ref "J9") (pin "4") (pinfunction "ID_4") (pintype "bidirectional"))
    )
  )
)
